# Power.net
KiCad netlist of a schematic drawn in Altium Designer
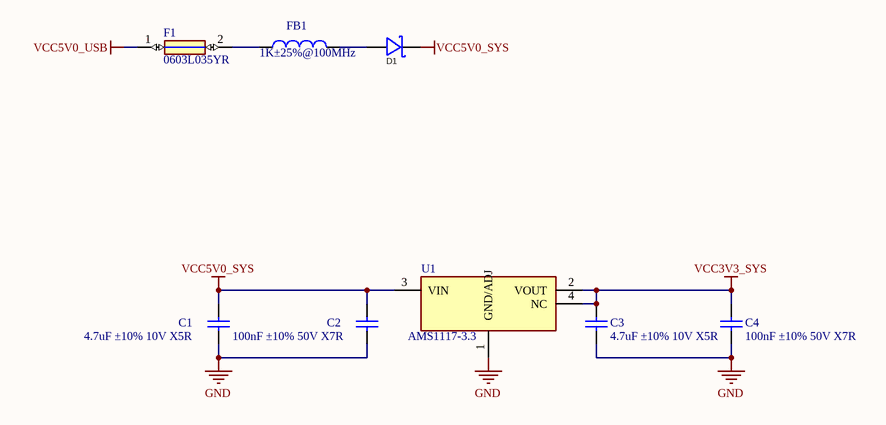
[diagram p0: Power.SchDoc]

(export (version "E")
  (design (tool "Eeschema 10.0.6"))
  (components
    (comp (ref "C1")
      (value "4.7uF ±10% 10V X5R")
      (footprint "C0402")
      (description "CL05A475KP5NRNC")
      (fields (field (name "PUBLISHER") "Altium Limited"))
      (libsource (lib "Component") (part "Cap"))
    )
    (comp (ref "C2")
      (value "100nF ±10% 50V X7R")
      (footprint "C0402")
      (description "CL05B104KO5NNNC")
      (fields (field (name "PUBLISHER") "Altium Limited"))
      (libsource (lib "Component") (part "Cap"))
    )
    (comp (ref "C3")
      (value "4.7uF ±10% 10V X5R")
      (footprint "C0402")
      (description "CL05A475KP5NRNC")
      (fields (field (name "PUBLISHER") "Altium Limited"))
      (libsource (lib "Component") (part "Cap"))
    )
    (comp (ref "C4")
      (value "100nF ±10% 50V X7R")
      (footprint "C0402")
      (description "CL05B104KO5NNNC")
      (fields (field (name "PUBLISHER") "Altium Limited"))
      (libsource (lib "Component") (part "Cap"))
    )
    (comp (ref "D1")
      (value "B340A-13-F")
      (footprint "SMA_L4.4-W2.6-LS5.0-RD")
      (description "直流反向耐压(Vr):40V;平均整流电流(Io):3A;正向压降(Vf):500mV@3A;")
      (fields (field (name "MANUFACTURER") "DIODES(美台)"))
      (libsource (lib "Component") (part "Diode_Schottky"))
    )
    (comp (ref "F1")
      (value "0603L035YR")
      (footprint "SamacSys:FUSC1608X75N")
      (description "Fuse")
      (fields (field (name "MOUSER PART NUMBER") "576-0603L035YR"))
      (libsource (lib "*") (part "0603L035YR"))
    )
    (comp (ref "FB1")
      (value "1K±25%@100MHz")
      (footprint "SamacSys:BLM18SP221SN1B")
      (description "BLM21AG102SN1D")
      (fields (field (name "PUBLISHER") "Altium Limited"))
      (libsource (lib "Miscellaneous Devices") (part "Inductor"))
    )
    (comp (ref "U1")
      (value "AMS1117-3.3")
      (footprint "SamacSys:SOT-223-4_L6.5-W3.5-P2.30-LS7.0-BR")
      (description "Integrated Circuit")
      (libsource (lib "SamacSys") (part "AMS1117-3.3"))
    )
  )
  (nets
    (net (code "1") (name "GND") (class "Default")
      (node (ref "C1") (pin "1") (pinfunction "1_1") (pintype "passive"))
      (node (ref "C2") (pin "1") (pinfunction "1_1") (pintype "passive"))
      (node (ref "C3") (pin "1") (pinfunction "1_1") (pintype "passive"))
      (node (ref "C4") (pin "1") (pinfunction "1_1") (pintype "passive"))
      (node (ref "U1") (pin "1") (pinfunction "GND/ADJ_1") (pintype "passive"))
    )
    (net (code "2") (name "Net-(D1-A)") (class "Default")
      (node (ref "D1") (pin "2") (pinfunction "A_2") (pintype "passive"))
      (node (ref "FB1") (pin "2") (pinfunction "2_2") (pintype "passive"))
    )
    (net (code "3") (name "Net-(F1-Pad2)") (class "Default")
      (node (ref "F1") (pin "2") (pinfunction "2_2") (pintype "bidirectional"))
      (node (ref "FB1") (pin "1") (pinfunction "1_1") (pintype "passive"))
    )
    (net (code "4") (name "VCC3V3_SYS") (class "Default")
      (node (ref "C3") (pin "2") (pinfunction "2_2") (pintype "passive"))
      (node (ref "C4") (pin "2") (pinfunction "2_2") (pintype "passive"))
      (node (ref "U1") (pin "2") (pinfunction "VOUT_2") (pintype "passive"))
      (node (ref "U1") (pin "4") (pinfunction "NC_4") (pintype "passive"))
    )
    (net (code "5") (name "VCC5V0_SYS") (class "Default")
      (node (ref "C1") (pin "2") (pinfunction "2_2") (pintype "passive"))
      (node (ref "C2") (pin "2") (pinfunction "2_2") (pintype "passive"))
      (node (ref "D1") (pin "1") (pinfunction "K_1") (pintype "passive"))
      (node (ref "U1") (pin "3") (pinfunction "VIN_3") (pintype "passive"))
    )
    (net (code "6") (name "VCC5V0_USB") (class "Default")
      (node (ref "F1") (pin "1") (pinfunction "1_1") (pintype "bidirectional"))
    )
  )
)
